# ProPrj_PW4040__2025-08-08-15-28-32.net
KiCad netlist of a schematic drawn in EasyEDA Pro
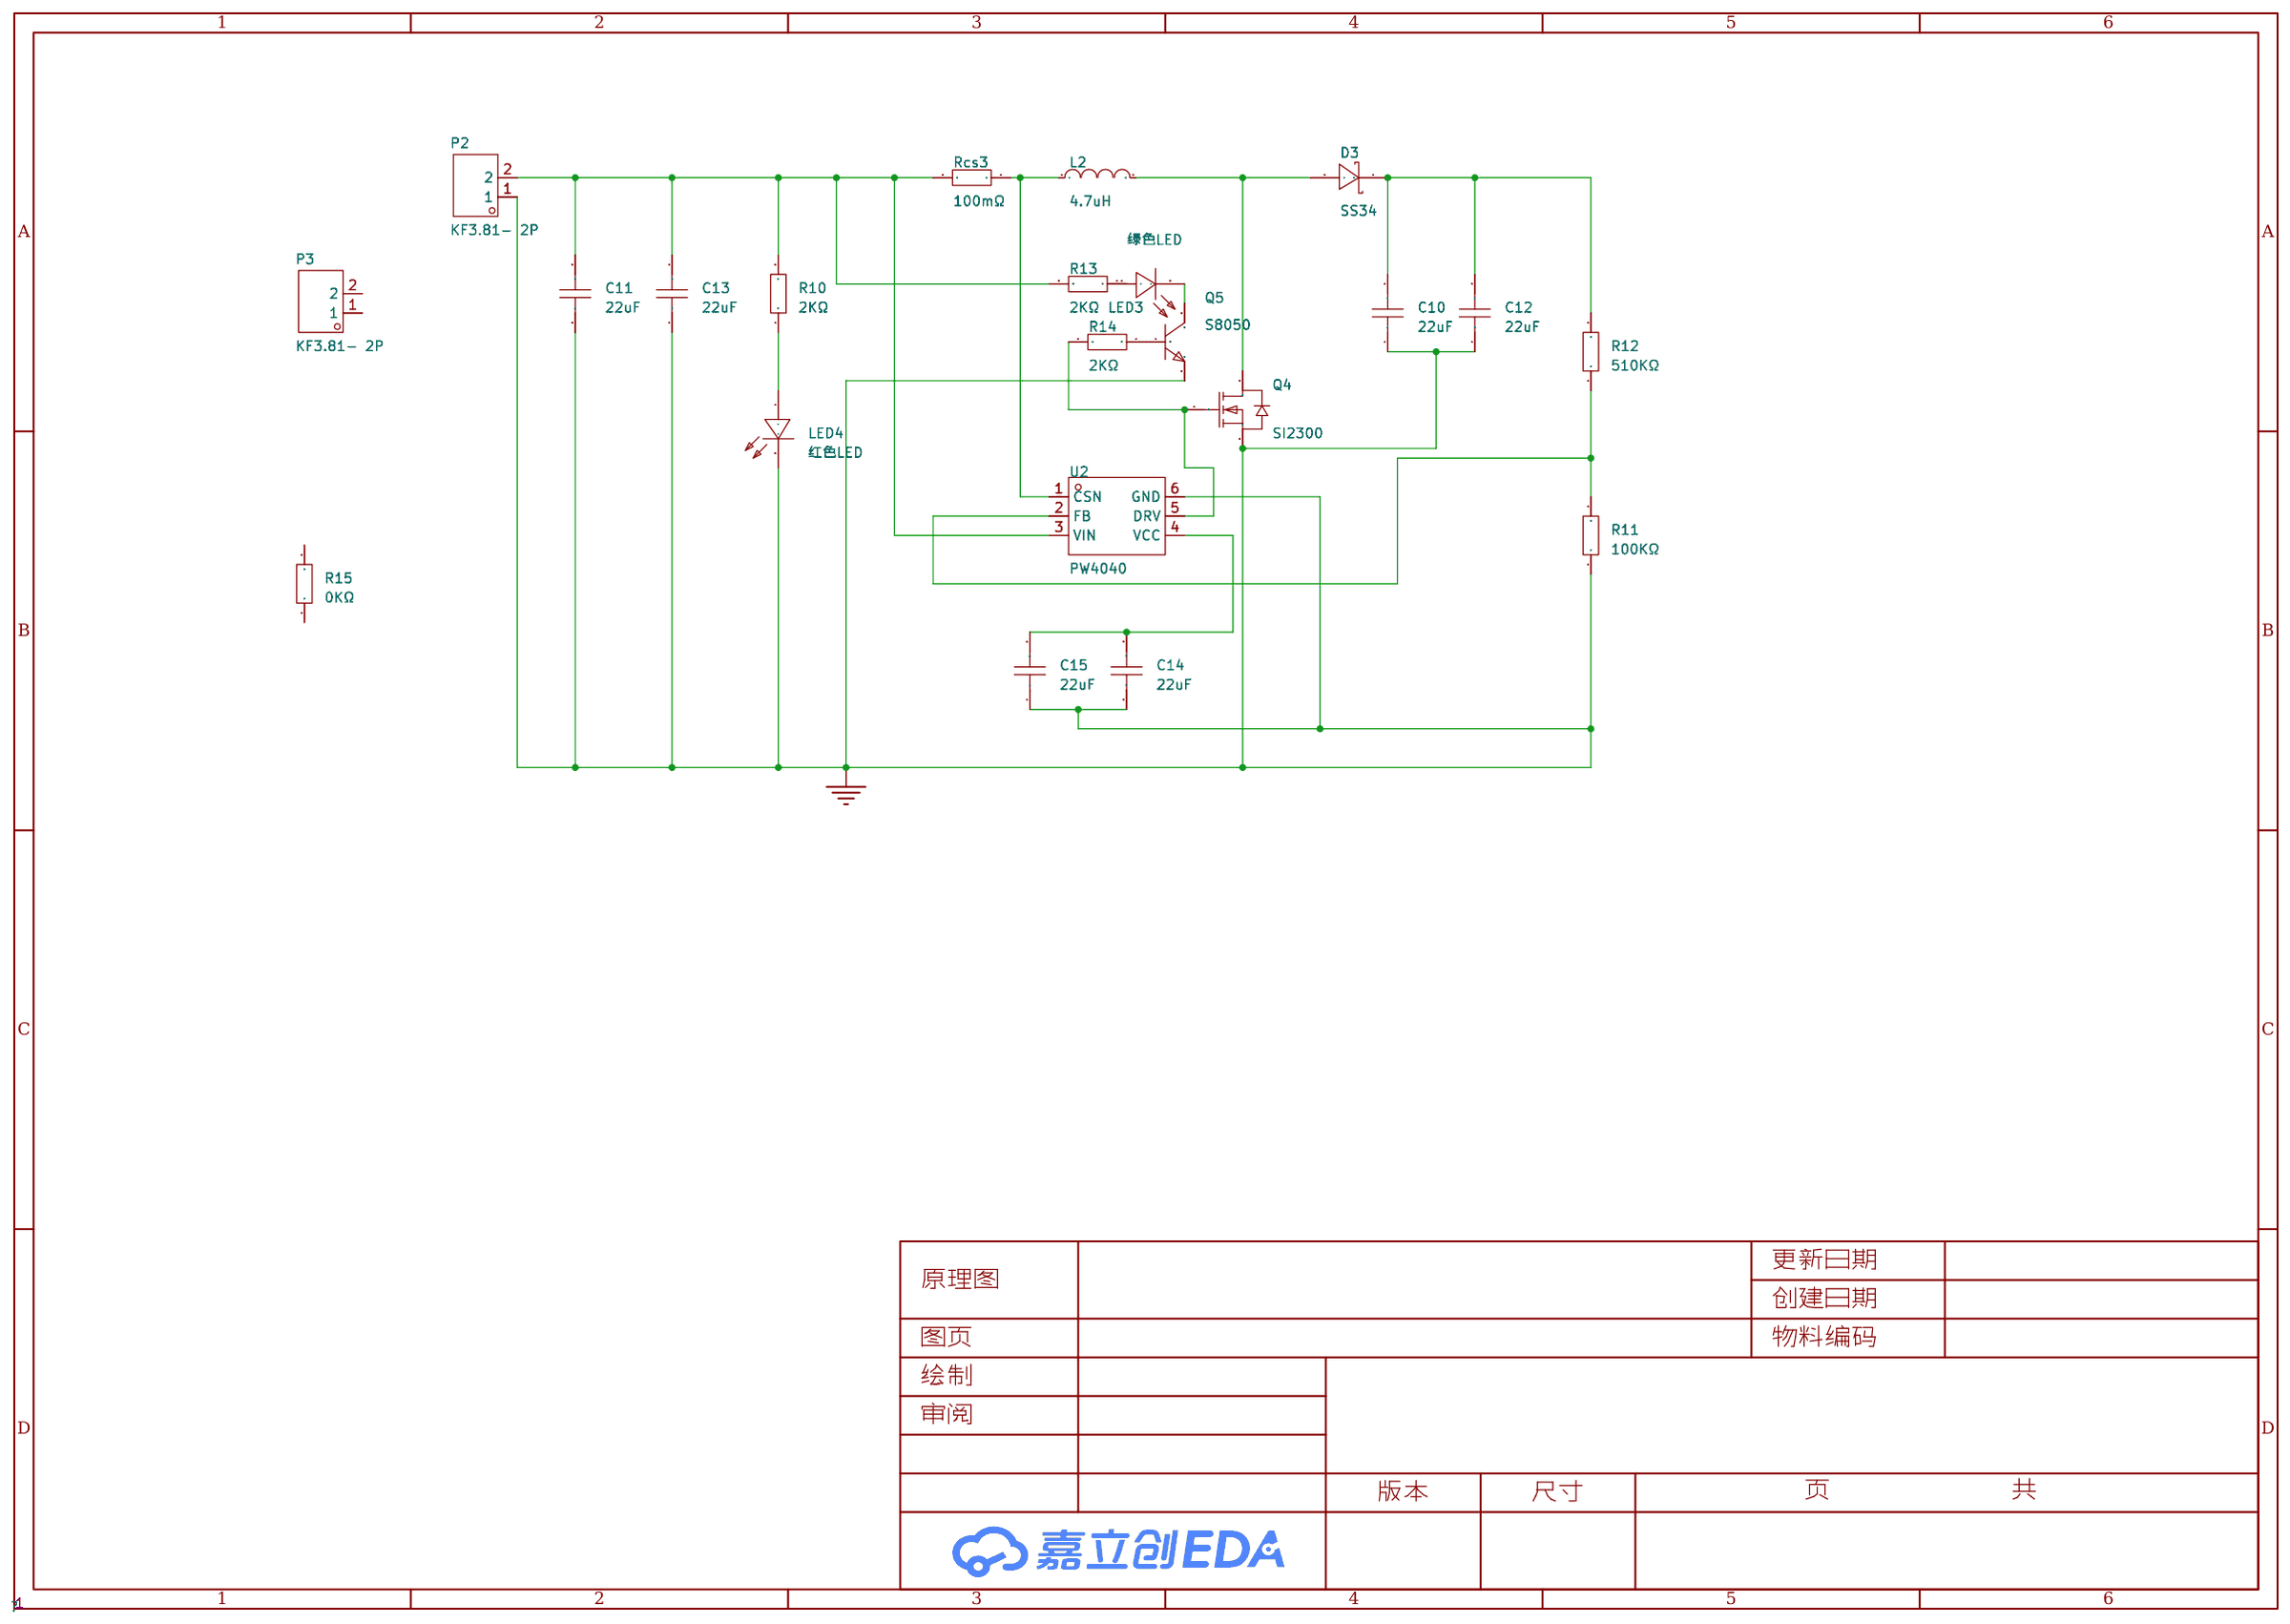
[diagram p0: schematic sheet]

(export (version "E")
  (design (tool "Eeschema 10.0.6"))
  (components
    (comp (ref "C10")
      (value "22uF")
      (footprint "easyedapro:C0805")
      (fields
        (field (name "Manufacturer Part") "GRM21BR61H106KE43L")
        (field (name "Manufacturer") "muRata(村田)")
      )
      (libsource (lib "easyedapro") (part "GRM21BR61H106KE43L"))
    )
    (comp (ref "C11")
      (value "22uF")
      (footprint "easyedapro:C0805")
      (fields
        (field (name "Manufacturer Part") "GRM21BR61H106KE43L")
        (field (name "Manufacturer") "muRata(村田)")
      )
      (libsource (lib "easyedapro") (part "GRM21BR61H106KE43L"))
    )
    (comp (ref "C12")
      (value "22uF")
      (footprint "easyedapro:C0805")
      (fields
        (field (name "Manufacturer Part") "GRM21BR61H106KE43L")
        (field (name "Manufacturer") "muRata(村田)")
      )
      (libsource (lib "easyedapro") (part "GRM21BR61H106KE43L"))
    )
    (comp (ref "C13")
      (value "22uF")
      (footprint "easyedapro:C0805")
      (fields
        (field (name "Manufacturer Part") "GRM21BR61H106KE43L")
        (field (name "Manufacturer") "muRata(村田)")
      )
      (libsource (lib "easyedapro") (part "GRM21BR61H106KE43L"))
    )
    (comp (ref "C14")
      (value "22uF")
      (footprint "easyedapro:C0805")
      (fields
        (field (name "Manufacturer Part") "GRM21BR61H106KE43L")
        (field (name "Manufacturer") "muRata(村田)")
      )
      (libsource (lib "easyedapro") (part "GRM21BR61H106KE43L"))
    )
    (comp (ref "C15")
      (value "22uF")
      (footprint "easyedapro:C0805")
      (fields
        (field (name "Manufacturer Part") "GRM21BR61H106KE43L")
        (field (name "Manufacturer") "muRata(村田)")
      )
      (libsource (lib "easyedapro") (part "GRM21BR61H106KE43L"))
    )
    (comp (ref "D3")
      (value "SS34")
      (footprint "easyedapro:SMA_L4.3-W2.6-LS5.2-RD")
      (fields (field (name "Manufacturer") "MDD(辰达半导体)"))
      (libsource (lib "easyedapro") (part "SS34_C8678"))
    )
    (comp (ref "L2")
      (value "4.7uH")
      (footprint "easyedapro:IND-SMD_L5.4-W5.2_FXL0530")
      (fields (field (name "Manufacturer Part") "FXL0530-100-M") (field (name "Manufacturer") "cjiang(长江微电)"))
      (libsource (lib "easyedapro") (part "FXL0530-100-M"))
    )
    (comp (ref "LED3")
      (value "绿色LED")
      (footprint "easyedapro:LED0805-R-RD")
      (fields (field (name "Manufacturer Part") "NCD0805R1") (field (name "Manufacturer") "国星光电"))
      (libsource (lib "easyedapro") (part "FC-2012HRK-620D"))
    )
    (comp (ref "LED4")
      (value "红色LED")
      (footprint "easyedapro:LED0805-R-RD")
      (fields (field (name "Manufacturer Part") "NCD0805R1") (field (name "Manufacturer") "国星光电"))
      (libsource (lib "easyedapro") (part "FC-2012HRK-620D"))
    )
    (comp (ref "P2")
      (value "KF3.81- 2P")
      (footprint "easyedapro:CONN-TH_2P-P3.81_WJ15EDGRC-3.81-2P")
      (fields
        (field (name "Manufacturer Part") "WJ15EDGRC-3.81-2P")
        (field (name "Manufacturer") "KANGNEX(康奈克斯电气)")
      )
      (libsource (lib "easyedapro") (part "WJ15EDGRC-3.81-2P"))
    )
    (comp (ref "P3")
      (value "KF3.81- 2P")
      (footprint "easyedapro:CONN-TH_2P-P3.81_WJ15EDGRC-3.81-2P")
      (fields
        (field (name "Manufacturer Part") "WJ15EDGRC-3.81-2P")
        (field (name "Manufacturer") "KANGNEX(康奈克斯电气)")
      )
      (libsource (lib "easyedapro") (part "WJ15EDGRC-3.81-2P"))
    )
    (comp (ref "Q4")
      (value "SI2300")
      (footprint "easyedapro:SOT-23-3_L2.9-W1.6-P1.90-LS2.8-BR")
      (fields (field (name "Manufacturer Part") "SI2300DS-T1-GE3") (field (name "Manufacturer") "VISHAY(威世)"))
      (libsource (lib "easyedapro") (part "SI2300DS-T1-GE3"))
    )
    (comp (ref "Q5")
      (value "S8050")
      (footprint "easyedapro:SOT-23-3_L2.9-W1.3-P1.90-LS2.4-BR")
      (fields (field (name "Manufacturer") "Doeshare(德芯)"))
      (libsource (lib "easyedapro") (part "S8050_C2931719"))
    )
    (comp (ref "R10")
      (value "2KΩ")
      (footprint "easyedapro:R0805")
      (fields
        (field (name "Manufacturer Part") "0805W8F2403T5E")
        (field (name "Manufacturer") "UNI-ROYAL(厚声)")
      )
      (libsource (lib "easyedapro") (part "0805W8F2403T5E"))
    )
    (comp (ref "R11")
      (value "100KΩ")
      (footprint "easyedapro:R0805")
      (fields
        (field (name "Manufacturer Part") "0805W8F2403T5E")
        (field (name "Manufacturer") "UNI-ROYAL(厚声)")
      )
      (libsource (lib "easyedapro") (part "0805W8F2403T5E"))
    )
    (comp (ref "R12")
      (value "510KΩ")
      (footprint "easyedapro:R0805")
      (fields
        (field (name "Manufacturer Part") "0805W8F2403T5E")
        (field (name "Manufacturer") "UNI-ROYAL(厚声)")
      )
      (libsource (lib "easyedapro") (part "0805W8F2403T5E"))
    )
    (comp (ref "R13")
      (value "2KΩ")
      (footprint "easyedapro:R0805")
      (fields
        (field (name "Manufacturer Part") "0805W8F2403T5E")
        (field (name "Manufacturer") "UNI-ROYAL(厚声)")
      )
      (libsource (lib "easyedapro") (part "0805W8F2403T5E"))
    )
    (comp (ref "R14")
      (value "2KΩ")
      (footprint "easyedapro:R0805")
      (fields
        (field (name "Manufacturer Part") "0805W8F2403T5E")
        (field (name "Manufacturer") "UNI-ROYAL(厚声)")
      )
      (libsource (lib "easyedapro") (part "0805W8F2403T5E"))
    )
    (comp (ref "R15")
      (value "0KΩ")
      (footprint "easyedapro:R0805")
      (fields
        (field (name "Manufacturer Part") "0805W8F2403T5E")
        (field (name "Manufacturer") "UNI-ROYAL(厚声)")
      )
      (libsource (lib "easyedapro") (part "0805W8F2403T5E"))
    )
    (comp (ref "Rcs3")
      (value "100mΩ")
      (footprint "easyedapro:R2512")
      (fields
        (field (name "Manufacturer Part") "25121WF100LT4E")
        (field (name "Manufacturer") "UNI-ROYAL(厚声)")
      )
      (libsource (lib "easyedapro") (part "25121WF100LT4E"))
    )
    (comp (ref "U2")
      (value "PW4040")
      (footprint "easyedapro:SOT-23-6_L2.9-W1.6-P0.95-LS2.8-BR")
      (libsource (lib "easyedapro") (part "PW4040"))
    )
  )
  (nets
    (net (code "1") (name "GND") (class "Default")
      (node (ref "C10") (pin "1") (pinfunction "1_1") (pintype "unspecified"))
      (node (ref "C11") (pin "1") (pinfunction "1_1") (pintype "unspecified"))
      (node (ref "C12") (pin "1") (pinfunction "1_1") (pintype "unspecified"))
      (node (ref "C13") (pin "1") (pinfunction "1_1") (pintype "unspecified"))
      (node (ref "C14") (pin "1") (pinfunction "1_1") (pintype "unspecified"))
      (node (ref "C15") (pin "1") (pinfunction "1_1") (pintype "unspecified"))
      (node (ref "LED4") (pin "2") (pinfunction "-_2") (pintype "unspecified"))
      (node (ref "P2") (pin "1") (pinfunction "1_1") (pintype "unspecified"))
      (node (ref "Q4") (pin "2") (pinfunction "S_2") (pintype "unspecified"))
      (node (ref "Q5") (pin "2") (pinfunction "E_2") (pintype "input"))
      (node (ref "R11") (pin "1") (pinfunction "1_1") (pintype "input"))
      (node (ref "U2") (pin "6") (pinfunction "GND_6") (pintype "unspecified"))
    )
    (net (code "2") (name "Net-(D3-A)") (class "Default")
      (node (ref "D3") (pin "2") (pinfunction "A_2") (pintype "unspecified"))
      (node (ref "L2") (pin "2") (pinfunction "2_2") (pintype "unspecified"))
      (node (ref "Q4") (pin "3") (pinfunction "D_3") (pintype "unspecified"))
    )
    (net (code "3") (name "Net-(D3-K)") (class "Default")
      (node (ref "C10") (pin "2") (pinfunction "2_2") (pintype "unspecified"))
      (node (ref "C12") (pin "2") (pinfunction "2_2") (pintype "unspecified"))
      (node (ref "D3") (pin "1") (pinfunction "K_1") (pintype "unspecified"))
      (node (ref "R12") (pin "2") (pinfunction "2_2") (pintype "input"))
    )
    (net (code "4") (name "Net-(LED3-+)") (class "Default")
      (node (ref "LED3") (pin "1") (pinfunction "+_1") (pintype "unspecified"))
      (node (ref "R13") (pin "1") (pinfunction "1_1") (pintype "input"))
    )
    (net (code "5") (name "Net-(LED3--)") (class "Default")
      (node (ref "LED3") (pin "2") (pinfunction "-_2") (pintype "unspecified"))
      (node (ref "Q5") (pin "3") (pinfunction "C_3") (pintype "input"))
    )
    (net (code "6") (name "Net-(LED4-+)") (class "Default")
      (node (ref "LED4") (pin "1") (pinfunction "+_1") (pintype "unspecified"))
      (node (ref "R10") (pin "1") (pinfunction "1_1") (pintype "input"))
    )
    (net (code "7") (name "Net-(Q4-G)") (class "Default")
      (node (ref "Q4") (pin "1") (pinfunction "G_1") (pintype "unspecified"))
      (node (ref "R14") (pin "2") (pinfunction "2_2") (pintype "input"))
      (node (ref "U2") (pin "5") (pinfunction "DRV_5") (pintype "unspecified"))
    )
    (net (code "8") (name "Net-(Q5-B)") (class "Default")
      (node (ref "Q5") (pin "1") (pinfunction "B_1") (pintype "input"))
      (node (ref "R14") (pin "1") (pinfunction "1_1") (pintype "input"))
    )
    (net (code "9") (name "Net-(U2-CSN)") (class "Default")
      (node (ref "L2") (pin "1") (pinfunction "1_1") (pintype "unspecified"))
      (node (ref "Rcs3") (pin "1") (pinfunction "1_1") (pintype "input"))
      (node (ref "U2") (pin "1") (pinfunction "CSN_1") (pintype "unspecified"))
    )
    (net (code "10") (name "Net-(U2-FB)") (class "Default")
      (node (ref "R11") (pin "2") (pinfunction "2_2") (pintype "input"))
      (node (ref "R12") (pin "1") (pinfunction "1_1") (pintype "input"))
      (node (ref "U2") (pin "2") (pinfunction "FB_2") (pintype "unspecified"))
    )
    (net (code "11") (name "Net-(U2-VCC)") (class "Default")
      (node (ref "C14") (pin "2") (pinfunction "2_2") (pintype "unspecified"))
      (node (ref "C15") (pin "2") (pinfunction "2_2") (pintype "unspecified"))
      (node (ref "U2") (pin "4") (pinfunction "VCC_4") (pintype "unspecified"))
    )
    (net (code "12") (name "Net-(U2-VIN)") (class "Default")
      (node (ref "C11") (pin "2") (pinfunction "2_2") (pintype "unspecified"))
      (node (ref "C13") (pin "2") (pinfunction "2_2") (pintype "unspecified"))
      (node (ref "P2") (pin "2") (pinfunction "2_2") (pintype "unspecified"))
      (node (ref "R10") (pin "2") (pinfunction "2_2") (pintype "input"))
      (node (ref "R13") (pin "2") (pinfunction "2_2") (pintype "input"))
      (node (ref "Rcs3") (pin "2") (pinfunction "2_2") (pintype "input"))
      (node (ref "U2") (pin "3") (pinfunction "VIN_3") (pintype "unspecified"))
    )
    (net (code "13") (name "unconnected-(P3-Pad1)") (class "Default")
      (node (ref "P3") (pin "1") (pinfunction "1_1") (pintype "unspecified"))
    )
    (net (code "14") (name "unconnected-(P3-Pad2)") (class "Default")
      (node (ref "P3") (pin "2") (pinfunction "2_2") (pintype "unspecified"))
    )
    (net (code "15") (name "unconnected-(R15-Pad1)") (class "Default")
      (node (ref "R15") (pin "1") (pinfunction "1_1") (pintype "input"))
    )
    (net (code "16") (name "unconnected-(R15-Pad2)") (class "Default")
      (node (ref "R15") (pin "2") (pinfunction "2_2") (pintype "input"))
    )
  )
)
